# sequencer_main.net
KiCad netlist of a schematic drawn in EAGLE
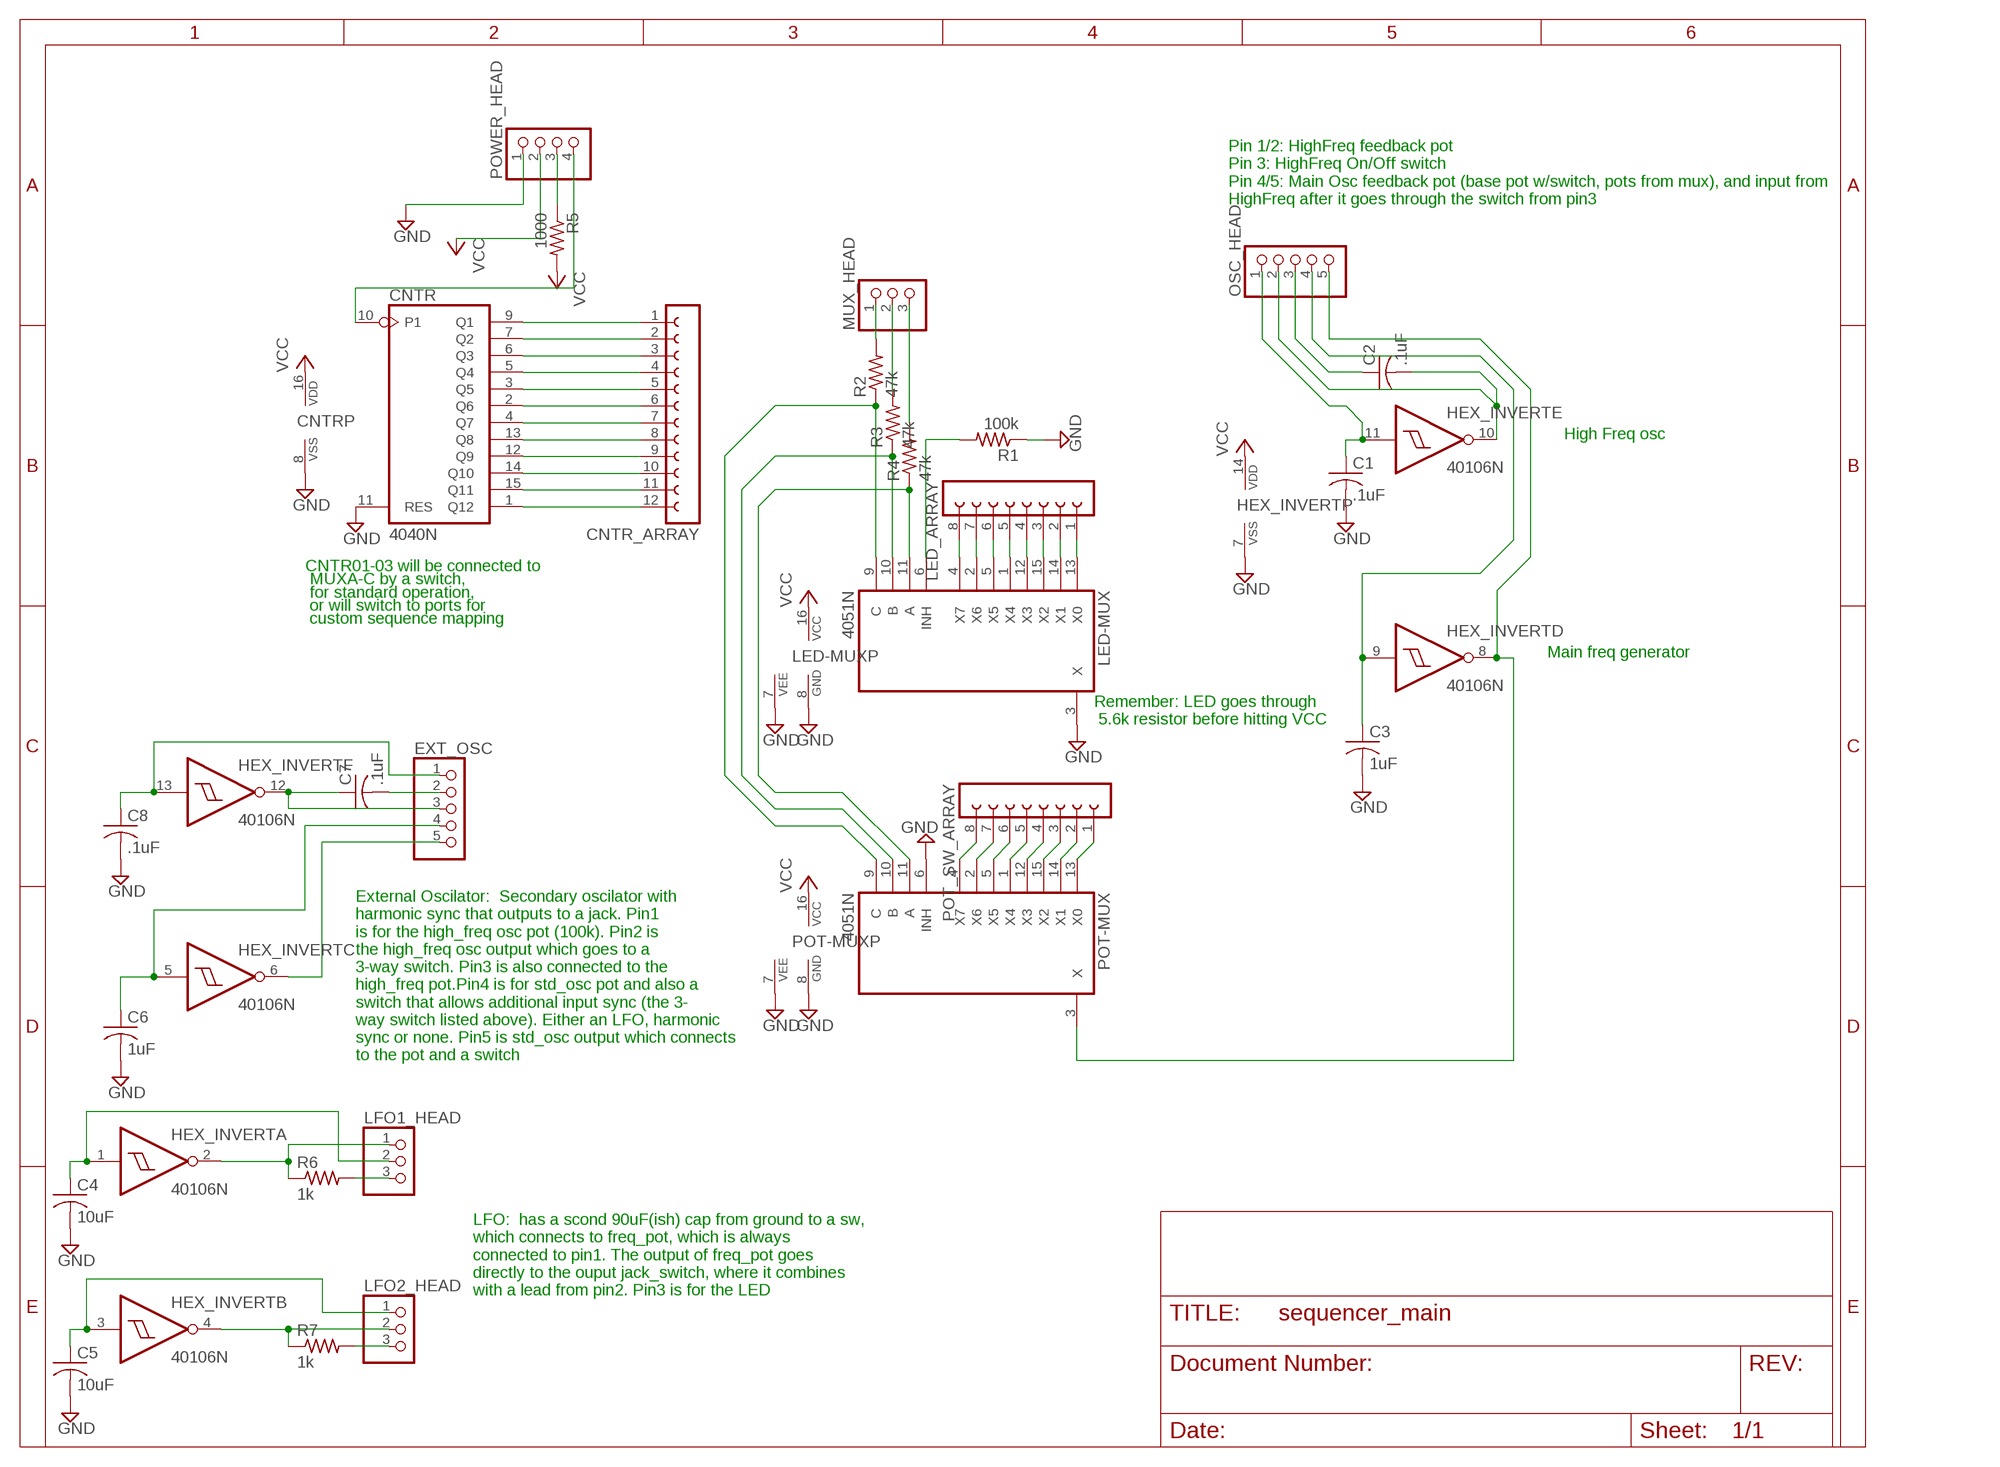
[diagram p0: schematic, sheet 1]

(export (version "E")
  (design (tool "Eeschema 10.0.6"))
  (components
    (comp (ref "C1")
      (value ".1uF")
      (footprint "eagle-import:C025-025X050")
      (libsource (lib "eagle-import") (part "C-US025-025X050"))
    )
    (comp (ref "C2")
      (value ".1uF")
      (footprint "eagle-import:C025-025X050")
      (libsource (lib "eagle-import") (part "C-US025-025X050"))
    )
    (comp (ref "C3")
      (value "1uF")
      (footprint "eagle-import:C025-025X050")
      (libsource (lib "eagle-import") (part "C-US025-025X050"))
    )
    (comp (ref "C4")
      (value "10uF")
      (footprint "eagle-import:C025-025X050")
      (libsource (lib "eagle-import") (part "C-US025-025X050"))
    )
    (comp (ref "C5")
      (value "10uF")
      (footprint "eagle-import:C025-025X050")
      (libsource (lib "eagle-import") (part "C-US025-025X050"))
    )
    (comp (ref "C6")
      (value "1uF")
      (footprint "eagle-import:C025-025X050")
      (libsource (lib "eagle-import") (part "C-US025-025X050"))
    )
    (comp (ref "C7")
      (value ".1uF")
      (footprint "eagle-import:C025-025X050")
      (libsource (lib "eagle-import") (part "C-US025-025X050"))
    )
    (comp (ref "C8")
      (value ".1uF")
      (footprint "eagle-import:C025-025X050")
      (libsource (lib "eagle-import") (part "C-US025-025X050"))
    )
    (comp (ref "CNTR")
      (value "4040N")
      (footprint "eagle-import:DIL16")
      (libsource (lib "eagle-import") (part "4040N"))
    )
    (comp (ref "CNTR_ARRAY")
      (value "FE12-1")
      (footprint "eagle-import:FE12")
      (libsource (lib "eagle-import") (part "FE12-1"))
    )
    (comp (ref "EXT_OSC")
      (value "PINHD-1X5")
      (footprint "eagle-import:1X05")
      (libsource (lib "eagle-import") (part "PINHD-1X5"))
    )
    (comp (ref "HEX_INVERT")
      (value "40106N")
      (footprint "eagle-import:DIL14")
      (libsource (lib "eagle-import") (part "40106N"))
    )
    (comp (ref "LED-MUX")
      (value "4051N")
      (footprint "eagle-import:DIL16")
      (libsource (lib "eagle-import") (part "4051N"))
    )
    (comp (ref "LED_ARRAY")
      (value "FE08-1")
      (footprint "eagle-import:FE08")
      (libsource (lib "eagle-import") (part "FE08-1"))
    )
    (comp (ref "LFO1_HEAD")
      (value "PINHD-1X3")
      (footprint "eagle-import:1X03")
      (libsource (lib "eagle-import") (part "PINHD-1X3"))
    )
    (comp (ref "LFO2_HEAD")
      (value "PINHD-1X3")
      (footprint "eagle-import:1X03")
      (libsource (lib "eagle-import") (part "PINHD-1X3"))
    )
    (comp (ref "MUX_HEAD")
      (value "PINHD-1X3")
      (footprint "eagle-import:1X03")
      (libsource (lib "eagle-import") (part "PINHD-1X3"))
    )
    (comp (ref "OSC_HEAD")
      (value "PINHD-1X5")
      (footprint "eagle-import:1X05")
      (libsource (lib "eagle-import") (part "PINHD-1X5"))
    )
    (comp (ref "POT-MUX")
      (value "4051N")
      (footprint "eagle-import:DIL16")
      (libsource (lib "eagle-import") (part "4051N"))
    )
    (comp (ref "POT_SW_ARRAY")
      (value "FE08-1")
      (footprint "eagle-import:FE08")
      (libsource (lib "eagle-import") (part "FE08-1"))
    )
    (comp (ref "POWER_HEAD")
      (value "PINHD-1X4")
      (footprint "eagle-import:1X04")
      (libsource (lib "eagle-import") (part "PINHD-1X4"))
    )
    (comp (ref "R1")
      (value "100k")
      (footprint "eagle-import:0204_7")
      (libsource (lib "eagle-import") (part "R-US_0204/7"))
    )
    (comp (ref "R2")
      (value "47k")
      (footprint "eagle-import:0204_7")
      (libsource (lib "eagle-import") (part "R-US_0204/7"))
    )
    (comp (ref "R3")
      (value "47k")
      (footprint "eagle-import:0204_7")
      (libsource (lib "eagle-import") (part "R-US_0204/7"))
    )
    (comp (ref "R4")
      (value "47k")
      (footprint "eagle-import:0204_7")
      (libsource (lib "eagle-import") (part "R-US_0204/7"))
    )
    (comp (ref "R5")
      (value "1000")
      (footprint "eagle-import:0204_7")
      (libsource (lib "eagle-import") (part "R-US_0204/7"))
    )
    (comp (ref "R6")
      (value "1k")
      (footprint "eagle-import:0204_7")
      (libsource (lib "eagle-import") (part "R-US_0204/7"))
    )
    (comp (ref "R7")
      (value "1k")
      (footprint "eagle-import:0204_7")
      (libsource (lib "eagle-import") (part "R-US_0204/7"))
    )
  )
  (nets
    (net (code "1") (name "GND") (class "Default")
      (node (ref "C1") (pin "2") (pinfunction "2_2") (pintype "passive"))
      (node (ref "C3") (pin "2") (pinfunction "2_2") (pintype "passive"))
      (node (ref "C4") (pin "2") (pinfunction "2_2") (pintype "passive"))
      (node (ref "C5") (pin "2") (pinfunction "2_2") (pintype "passive"))
      (node (ref "C6") (pin "2") (pinfunction "2_2") (pintype "passive"))
      (node (ref "C8") (pin "2") (pinfunction "2_2") (pintype "passive"))
      (node (ref "CNTR") (pin "11") (pinfunction "RES_11") (pintype "input"))
      (node (ref "CNTR") (pin "8") (pinfunction "VSS_8") (pintype "power_in"))
      (node (ref "HEX_INVERT") (pin "7") (pinfunction "VSS_7") (pintype "power_in"))
      (node (ref "LED-MUX") (pin "3") (pinfunction "X_3") (pintype "bidirectional"))
      (node (ref "LED-MUX") (pin "7") (pinfunction "VEE_7") (pintype "power_in"))
      (node (ref "LED-MUX") (pin "8") (pinfunction "GND_8") (pintype "power_in"))
      (node (ref "POT-MUX") (pin "6") (pinfunction "INH_6") (pintype "input"))
      (node (ref "POT-MUX") (pin "7") (pinfunction "VEE_7") (pintype "power_in"))
      (node (ref "POT-MUX") (pin "8") (pinfunction "GND_8") (pintype "power_in"))
      (node (ref "POWER_HEAD") (pin "1") (pinfunction "1_1") (pintype "passive"))
      (node (ref "R1") (pin "1") (pinfunction "1_1") (pintype "passive"))
    )
    (net (code "2") (name "Net-(C2-Pad1)") (class "Default")
      (node (ref "C2") (pin "1") (pinfunction "1_1") (pintype "passive"))
      (node (ref "OSC_HEAD") (pin "3") (pinfunction "3_3") (pintype "passive"))
    )
    (net (code "3") (name "Net-(C7-Pad2)") (class "Default")
      (node (ref "C7") (pin "2") (pinfunction "2_2") (pintype "passive"))
      (node (ref "EXT_OSC") (pin "2") (pinfunction "2_2") (pintype "passive"))
    )
    (net (code "4") (name "Net-(CNTRA-P1)") (class "Default")
      (node (ref "CNTR") (pin "10") (pinfunction "P1_10") (pintype "input"))
      (node (ref "POWER_HEAD") (pin "4") (pinfunction "4_4") (pintype "passive"))
    )
    (net (code "5") (name "Net-(CNTRA-Q1)") (class "Default")
      (node (ref "CNTR") (pin "9") (pinfunction "Q1_9") (pintype "output"))
      (node (ref "CNTR_ARRAY") (pin "1") (pinfunction "1_1") (pintype "passive"))
    )
    (net (code "6") (name "Net-(CNTRA-Q2)") (class "Default")
      (node (ref "CNTR") (pin "7") (pinfunction "Q2_7") (pintype "output"))
      (node (ref "CNTR_ARRAY") (pin "2") (pinfunction "2_2") (pintype "passive"))
    )
    (net (code "7") (name "Net-(CNTRA-Q3)") (class "Default")
      (node (ref "CNTR") (pin "6") (pinfunction "Q3_6") (pintype "output"))
      (node (ref "CNTR_ARRAY") (pin "3") (pinfunction "3_3") (pintype "passive"))
    )
    (net (code "8") (name "Net-(CNTRA-Q4)") (class "Default")
      (node (ref "CNTR") (pin "5") (pinfunction "Q4_5") (pintype "output"))
      (node (ref "CNTR_ARRAY") (pin "4") (pinfunction "4_4") (pintype "passive"))
    )
    (net (code "9") (name "Net-(CNTRA-Q5)") (class "Default")
      (node (ref "CNTR") (pin "3") (pinfunction "Q5_3") (pintype "output"))
      (node (ref "CNTR_ARRAY") (pin "5") (pinfunction "5_5") (pintype "passive"))
    )
    (net (code "10") (name "Net-(CNTRA-Q6)") (class "Default")
      (node (ref "CNTR") (pin "2") (pinfunction "Q6_2") (pintype "output"))
      (node (ref "CNTR_ARRAY") (pin "6") (pinfunction "6_6") (pintype "passive"))
    )
    (net (code "11") (name "Net-(CNTRA-Q7)") (class "Default")
      (node (ref "CNTR") (pin "4") (pinfunction "Q7_4") (pintype "output"))
      (node (ref "CNTR_ARRAY") (pin "7") (pinfunction "7_7") (pintype "passive"))
    )
    (net (code "12") (name "Net-(CNTRA-Q8)") (class "Default")
      (node (ref "CNTR") (pin "13") (pinfunction "Q8_13") (pintype "output"))
      (node (ref "CNTR_ARRAY") (pin "8") (pinfunction "8_8") (pintype "passive"))
    )
    (net (code "13") (name "Net-(CNTRA-Q9)") (class "Default")
      (node (ref "CNTR") (pin "12") (pinfunction "Q9_12") (pintype "output"))
      (node (ref "CNTR_ARRAY") (pin "9") (pinfunction "9_9") (pintype "passive"))
    )
    (net (code "14") (name "Net-(CNTRA-Q10)") (class "Default")
      (node (ref "CNTR") (pin "14") (pinfunction "Q10_14") (pintype "output"))
      (node (ref "CNTR_ARRAY") (pin "10") (pinfunction "10_10") (pintype "passive"))
    )
    (net (code "15") (name "Net-(CNTRA-Q11)") (class "Default")
      (node (ref "CNTR") (pin "15") (pinfunction "Q11_15") (pintype "output"))
      (node (ref "CNTR_ARRAY") (pin "11") (pinfunction "11_11") (pintype "passive"))
    )
    (net (code "16") (name "Net-(CNTRA-Q12)") (class "Default")
      (node (ref "CNTR") (pin "1") (pinfunction "Q12_1") (pintype "output"))
      (node (ref "CNTR_ARRAY") (pin "12") (pinfunction "12_12") (pintype "passive"))
    )
    (net (code "17") (name "Net-(HEX_INVERTA-I)") (class "Default")
      (node (ref "C4") (pin "1") (pinfunction "1_1") (pintype "passive"))
      (node (ref "HEX_INVERT") (pin "1") (pinfunction "I_1") (pintype "input"))
      (node (ref "LFO1_HEAD") (pin "2") (pinfunction "2_2") (pintype "passive"))
    )
    (net (code "18") (name "Net-(HEX_INVERTA-O)") (class "Default")
      (node (ref "HEX_INVERT") (pin "2") (pinfunction "O_2") (pintype "output"))
      (node (ref "LFO1_HEAD") (pin "1") (pinfunction "1_1") (pintype "passive"))
      (node (ref "R6") (pin "1") (pinfunction "1_1") (pintype "passive"))
    )
    (net (code "19") (name "Net-(HEX_INVERTB-I)") (class "Default")
      (node (ref "C5") (pin "1") (pinfunction "1_1") (pintype "passive"))
      (node (ref "HEX_INVERT") (pin "3") (pinfunction "I_3") (pintype "input"))
      (node (ref "LFO2_HEAD") (pin "1") (pinfunction "1_1") (pintype "passive"))
    )
    (net (code "20") (name "Net-(HEX_INVERTB-O)") (class "Default")
      (node (ref "HEX_INVERT") (pin "4") (pinfunction "O_4") (pintype "output"))
      (node (ref "LFO2_HEAD") (pin "2") (pinfunction "2_2") (pintype "passive"))
      (node (ref "R7") (pin "1") (pinfunction "1_1") (pintype "passive"))
    )
    (net (code "21") (name "Net-(HEX_INVERTC-I)") (class "Default")
      (node (ref "C6") (pin "1") (pinfunction "1_1") (pintype "passive"))
      (node (ref "EXT_OSC") (pin "4") (pinfunction "4_4") (pintype "passive"))
      (node (ref "HEX_INVERT") (pin "5") (pinfunction "I_5") (pintype "input"))
    )
    (net (code "22") (name "Net-(HEX_INVERTC-O)") (class "Default")
      (node (ref "EXT_OSC") (pin "5") (pinfunction "5_5") (pintype "passive"))
      (node (ref "HEX_INVERT") (pin "6") (pinfunction "O_6") (pintype "output"))
    )
    (net (code "23") (name "Net-(HEX_INVERTD-I)") (class "Default")
      (node (ref "C3") (pin "1") (pinfunction "1_1") (pintype "passive"))
      (node (ref "HEX_INVERT") (pin "9") (pinfunction "I_9") (pintype "input"))
      (node (ref "OSC_HEAD") (pin "4") (pinfunction "4_4") (pintype "passive"))
    )
    (net (code "24") (name "Net-(HEX_INVERTD-O)") (class "Default")
      (node (ref "HEX_INVERT") (pin "8") (pinfunction "O_8") (pintype "output"))
      (node (ref "OSC_HEAD") (pin "5") (pinfunction "5_5") (pintype "passive"))
      (node (ref "POT-MUX") (pin "3") (pinfunction "X_3") (pintype "bidirectional"))
    )
    (net (code "25") (name "Net-(HEX_INVERTE-I)") (class "Default")
      (node (ref "C1") (pin "1") (pinfunction "1_1") (pintype "passive"))
      (node (ref "HEX_INVERT") (pin "11") (pinfunction "I_11") (pintype "input"))
      (node (ref "OSC_HEAD") (pin "1") (pinfunction "1_1") (pintype "passive"))
    )
    (net (code "26") (name "Net-(HEX_INVERTE-O)") (class "Default")
      (node (ref "C2") (pin "2") (pinfunction "2_2") (pintype "passive"))
      (node (ref "HEX_INVERT") (pin "10") (pinfunction "O_10") (pintype "output"))
      (node (ref "OSC_HEAD") (pin "2") (pinfunction "2_2") (pintype "passive"))
    )
    (net (code "27") (name "Net-(HEX_INVERTF-I)") (class "Default")
      (node (ref "C8") (pin "1") (pinfunction "1_1") (pintype "passive"))
      (node (ref "EXT_OSC") (pin "1") (pinfunction "1_1") (pintype "passive"))
      (node (ref "HEX_INVERT") (pin "13") (pinfunction "I_13") (pintype "input"))
    )
    (net (code "28") (name "Net-(HEX_INVERTF-O)") (class "Default")
      (node (ref "C7") (pin "1") (pinfunction "1_1") (pintype "passive"))
      (node (ref "EXT_OSC") (pin "3") (pinfunction "3_3") (pintype "passive"))
      (node (ref "HEX_INVERT") (pin "12") (pinfunction "O_12") (pintype "output"))
    )
    (net (code "29") (name "Net-(LED-MUXA-A)") (class "Default")
      (node (ref "LED-MUX") (pin "11") (pinfunction "A_11") (pintype "input"))
      (node (ref "POT-MUX") (pin "11") (pinfunction "A_11") (pintype "input"))
      (node (ref "R4") (pin "1") (pinfunction "1_1") (pintype "passive"))
    )
    (net (code "30") (name "Net-(LED-MUXA-B)") (class "Default")
      (node (ref "LED-MUX") (pin "10") (pinfunction "B_10") (pintype "input"))
      (node (ref "POT-MUX") (pin "10") (pinfunction "B_10") (pintype "input"))
      (node (ref "R3") (pin "1") (pinfunction "1_1") (pintype "passive"))
    )
    (net (code "31") (name "Net-(LED-MUXA-C)") (class "Default")
      (node (ref "LED-MUX") (pin "9") (pinfunction "C_9") (pintype "input"))
      (node (ref "POT-MUX") (pin "9") (pinfunction "C_9") (pintype "input"))
      (node (ref "R2") (pin "1") (pinfunction "1_1") (pintype "passive"))
    )
    (net (code "32") (name "Net-(LED-MUXA-INH)") (class "Default")
      (node (ref "LED-MUX") (pin "6") (pinfunction "INH_6") (pintype "input"))
      (node (ref "R1") (pin "2") (pinfunction "2_2") (pintype "passive"))
    )
    (net (code "33") (name "Net-(LED-MUXA-X0)") (class "Default")
      (node (ref "LED-MUX") (pin "13") (pinfunction "X0_13") (pintype "bidirectional"))
      (node (ref "LED_ARRAY") (pin "1") (pinfunction "1_1") (pintype "passive"))
    )
    (net (code "34") (name "Net-(LED-MUXA-X1)") (class "Default")
      (node (ref "LED-MUX") (pin "14") (pinfunction "X1_14") (pintype "bidirectional"))
      (node (ref "LED_ARRAY") (pin "2") (pinfunction "2_2") (pintype "passive"))
    )
    (net (code "35") (name "Net-(LED-MUXA-X2)") (class "Default")
      (node (ref "LED-MUX") (pin "15") (pinfunction "X2_15") (pintype "bidirectional"))
      (node (ref "LED_ARRAY") (pin "3") (pinfunction "3_3") (pintype "passive"))
    )
    (net (code "36") (name "Net-(LED-MUXA-X3)") (class "Default")
      (node (ref "LED-MUX") (pin "12") (pinfunction "X3_12") (pintype "bidirectional"))
      (node (ref "LED_ARRAY") (pin "4") (pinfunction "4_4") (pintype "passive"))
    )
    (net (code "37") (name "Net-(LED-MUXA-X4)") (class "Default")
      (node (ref "LED-MUX") (pin "1") (pinfunction "X4_1") (pintype "bidirectional"))
      (node (ref "LED_ARRAY") (pin "5") (pinfunction "5_5") (pintype "passive"))
    )
    (net (code "38") (name "Net-(LED-MUXA-X5)") (class "Default")
      (node (ref "LED-MUX") (pin "5") (pinfunction "X5_5") (pintype "bidirectional"))
      (node (ref "LED_ARRAY") (pin "6") (pinfunction "6_6") (pintype "passive"))
    )
    (net (code "39") (name "Net-(LED-MUXA-X6)") (class "Default")
      (node (ref "LED-MUX") (pin "2") (pinfunction "X6_2") (pintype "bidirectional"))
      (node (ref "LED_ARRAY") (pin "7") (pinfunction "7_7") (pintype "passive"))
    )
    (net (code "40") (name "Net-(LED-MUXA-X7)") (class "Default")
      (node (ref "LED-MUX") (pin "4") (pinfunction "X7_4") (pintype "bidirectional"))
      (node (ref "LED_ARRAY") (pin "8") (pinfunction "8_8") (pintype "passive"))
    )
    (net (code "41") (name "Net-(LFO1_HEAD-Pad3)") (class "Default")
      (node (ref "LFO1_HEAD") (pin "3") (pinfunction "3_3") (pintype "passive"))
      (node (ref "R6") (pin "2") (pinfunction "2_2") (pintype "passive"))
    )
    (net (code "42") (name "Net-(LFO2_HEAD-Pad3)") (class "Default")
      (node (ref "LFO2_HEAD") (pin "3") (pinfunction "3_3") (pintype "passive"))
      (node (ref "R7") (pin "2") (pinfunction "2_2") (pintype "passive"))
    )
    (net (code "43") (name "Net-(MUX_HEAD-Pad1)") (class "Default")
      (node (ref "MUX_HEAD") (pin "1") (pinfunction "1_1") (pintype "passive"))
      (node (ref "R2") (pin "2") (pinfunction "2_2") (pintype "passive"))
    )
    (net (code "44") (name "Net-(MUX_HEAD-Pad2)") (class "Default")
      (node (ref "MUX_HEAD") (pin "2") (pinfunction "2_2") (pintype "passive"))
      (node (ref "R3") (pin "2") (pinfunction "2_2") (pintype "passive"))
    )
    (net (code "45") (name "Net-(MUX_HEAD-Pad3)") (class "Default")
      (node (ref "MUX_HEAD") (pin "3") (pinfunction "3_3") (pintype "passive"))
      (node (ref "R4") (pin "2") (pinfunction "2_2") (pintype "passive"))
    )
    (net (code "46") (name "Net-(POT-MUXA-X0)") (class "Default")
      (node (ref "POT-MUX") (pin "13") (pinfunction "X0_13") (pintype "bidirectional"))
      (node (ref "POT_SW_ARRAY") (pin "1") (pinfunction "1_1") (pintype "passive"))
    )
    (net (code "47") (name "Net-(POT-MUXA-X1)") (class "Default")
      (node (ref "POT-MUX") (pin "14") (pinfunction "X1_14") (pintype "bidirectional"))
      (node (ref "POT_SW_ARRAY") (pin "2") (pinfunction "2_2") (pintype "passive"))
    )
    (net (code "48") (name "Net-(POT-MUXA-X2)") (class "Default")
      (node (ref "POT-MUX") (pin "15") (pinfunction "X2_15") (pintype "bidirectional"))
      (node (ref "POT_SW_ARRAY") (pin "3") (pinfunction "3_3") (pintype "passive"))
    )
    (net (code "49") (name "Net-(POT-MUXA-X3)") (class "Default")
      (node (ref "POT-MUX") (pin "12") (pinfunction "X3_12") (pintype "bidirectional"))
      (node (ref "POT_SW_ARRAY") (pin "4") (pinfunction "4_4") (pintype "passive"))
    )
    (net (code "50") (name "Net-(POT-MUXA-X4)") (class "Default")
      (node (ref "POT-MUX") (pin "1") (pinfunction "X4_1") (pintype "bidirectional"))
      (node (ref "POT_SW_ARRAY") (pin "5") (pinfunction "5_5") (pintype "passive"))
    )
    (net (code "51") (name "Net-(POT-MUXA-X5)") (class "Default")
      (node (ref "POT-MUX") (pin "5") (pinfunction "X5_5") (pintype "bidirectional"))
      (node (ref "POT_SW_ARRAY") (pin "6") (pinfunction "6_6") (pintype "passive"))
    )
    (net (code "52") (name "Net-(POT-MUXA-X6)") (class "Default")
      (node (ref "POT-MUX") (pin "2") (pinfunction "X6_2") (pintype "bidirectional"))
      (node (ref "POT_SW_ARRAY") (pin "7") (pinfunction "7_7") (pintype "passive"))
    )
    (net (code "53") (name "Net-(POT-MUXA-X7)") (class "Default")
      (node (ref "POT-MUX") (pin "4") (pinfunction "X7_4") (pintype "bidirectional"))
      (node (ref "POT_SW_ARRAY") (pin "8") (pinfunction "8_8") (pintype "passive"))
    )
    (net (code "54") (name "Net-(POWER_HEAD-Pad3)") (class "Default")
      (node (ref "POWER_HEAD") (pin "3") (pinfunction "3_3") (pintype "passive"))
      (node (ref "R5") (pin "1") (pinfunction "1_1") (pintype "passive"))
    )
    (net (code "55") (name "VCC") (class "Default")
      (node (ref "CNTR") (pin "16") (pinfunction "VDD_16") (pintype "power_in"))
      (node (ref "HEX_INVERT") (pin "14") (pinfunction "VDD_14") (pintype "power_in"))
      (node (ref "LED-MUX") (pin "16") (pinfunction "VCC_16") (pintype "power_in"))
      (node (ref "POT-MUX") (pin "16") (pinfunction "VCC_16") (pintype "power_in"))
      (node (ref "POWER_HEAD") (pin "2") (pinfunction "2_2") (pintype "passive"))
      (node (ref "R5") (pin "2") (pinfunction "2_2") (pintype "passive"))
    )
  )
)
